# LB77.net
KiCad netlist of a schematic drawn in Altium Designer
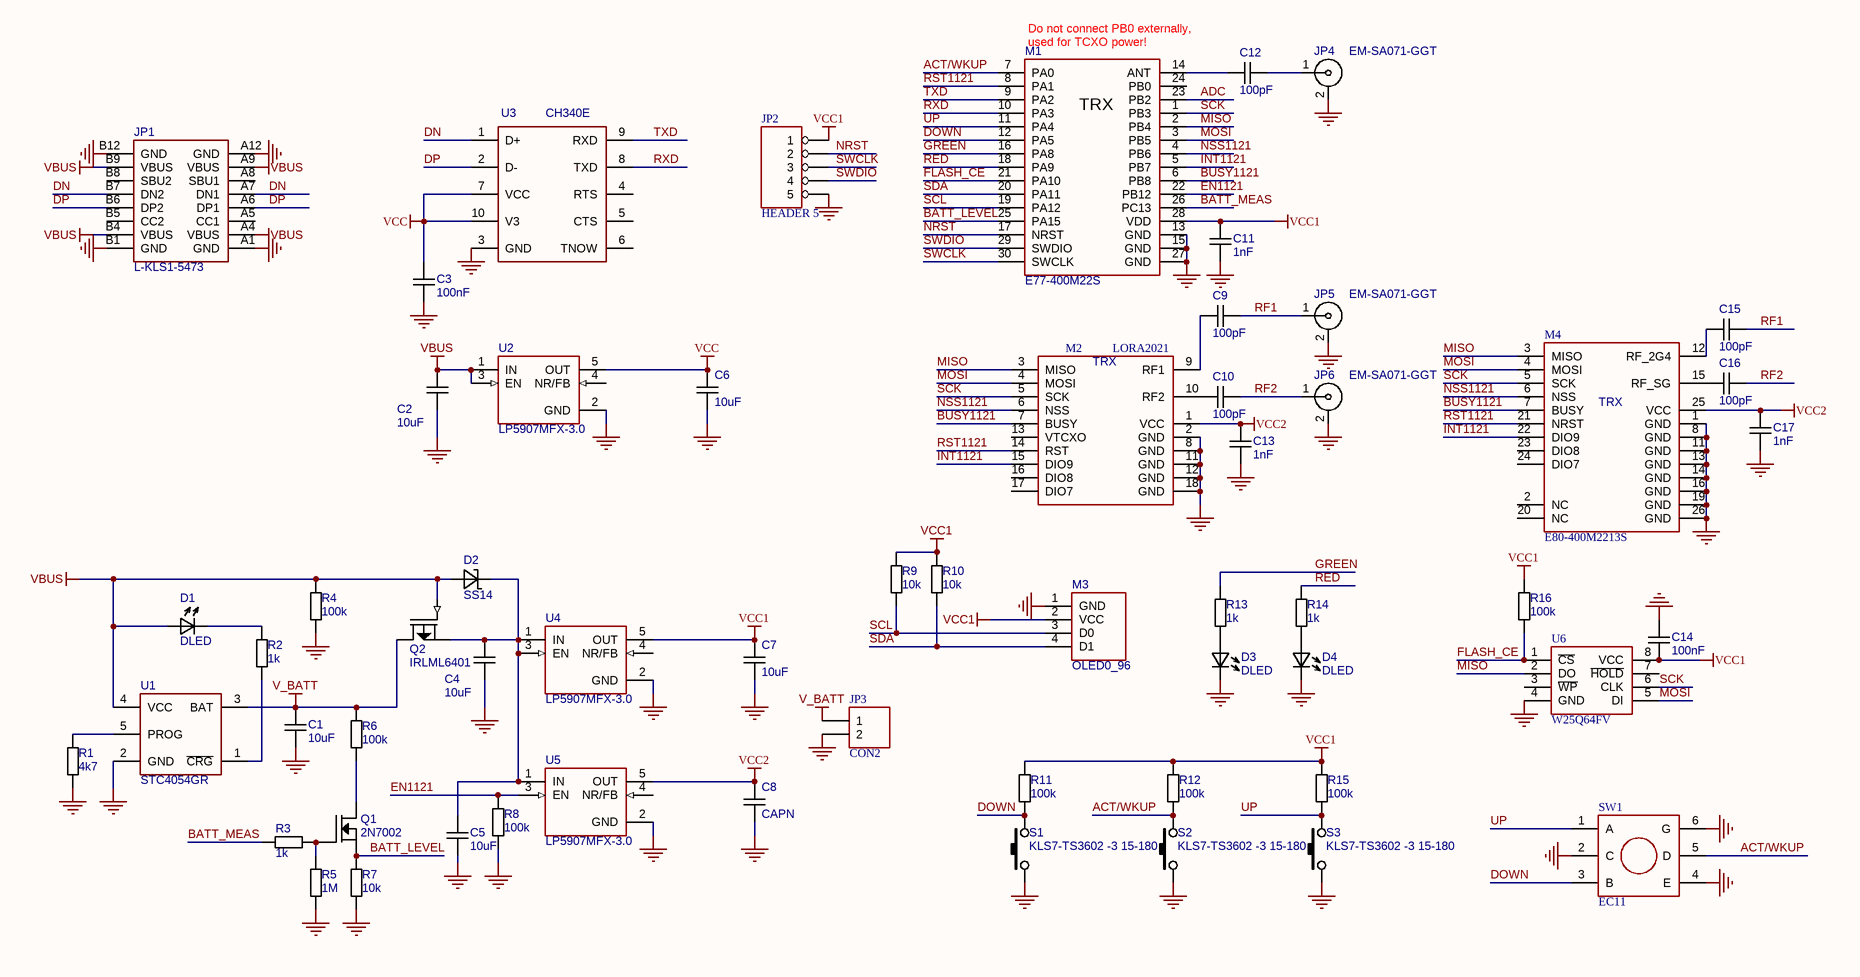
[diagram p0: LB77.SchDoc]

(export (version "E")
  (design (tool "Eeschema 10.0.6"))
  (components
    (comp (ref "C1")
      (value "10uF")
      (footprint "C-0805")
      (fields (field (name "VOLTAGE") "50V"))
      (libsource (lib "Passive") (part "CAPN"))
    )
    (comp (ref "C2")
      (value "10uF")
      (footprint "C-0805")
      (fields (field (name "VOLTAGE") "50V"))
      (libsource (lib "Passive") (part "CAPN"))
    )
    (comp (ref "C3")
      (value "100nF")
      (footprint "C-0603")
      (fields (field (name "VOLTAGE") "50V"))
      (libsource (lib "Passive") (part "CAPN"))
    )
    (comp (ref "C4")
      (value "10uF")
      (footprint "C-0805")
      (fields (field (name "VOLTAGE") "50V"))
      (libsource (lib "Passive") (part "CAPN"))
    )
    (comp (ref "C5")
      (value "10uF")
      (footprint "C-0805")
      (fields (field (name "VOLTAGE") "50V"))
      (libsource (lib "Passive") (part "CAPN"))
    )
    (comp (ref "C6")
      (value "10uF")
      (footprint "C-0805")
      (fields (field (name "VOLTAGE") "50V"))
      (libsource (lib "Passive") (part "CAPN"))
    )
    (comp (ref "C7")
      (value "10uF")
      (footprint "C-0805")
      (fields (field (name "VOLTAGE") "50V"))
      (libsource (lib "Passive") (part "CAPN"))
    )
    (comp (ref "C8")
      (value "CAPN")
      (footprint "C-0805")
      (fields (field (name "VOLTAGE") "50V"))
      (libsource (lib "Passive") (part "CAPN"))
    )
    (comp (ref "C9")
      (value "100pF")
      (footprint "C-0603")
      (fields (field (name "VOLTAGE") "50V"))
      (libsource (lib "Passive") (part "CAPN"))
    )
    (comp (ref "C10")
      (value "100pF")
      (footprint "C-0603")
      (fields (field (name "VOLTAGE") "50V"))
      (libsource (lib "Passive") (part "CAPN"))
    )
    (comp (ref "C11")
      (value "1nF")
      (footprint "C-0603")
      (fields (field (name "VOLTAGE") "50V"))
      (libsource (lib "Passive") (part "CAPN"))
    )
    (comp (ref "C12")
      (value "100pF")
      (footprint "C-0603")
      (fields (field (name "VOLTAGE") "50V"))
      (libsource (lib "Passive") (part "CAPN"))
    )
    (comp (ref "C13")
      (value "1nF")
      (footprint "C-0603")
      (fields (field (name "VOLTAGE") "50V"))
      (libsource (lib "Passive") (part "CAPN"))
    )
    (comp (ref "C14")
      (value "100nF")
      (footprint "C-0603")
      (fields (field (name "VOLTAGE") "50V"))
      (libsource (lib "Passive") (part "CAPN"))
    )
    (comp (ref "C15")
      (value "100pF")
      (footprint "C-0603")
      (fields (field (name "VOLTAGE") "50V"))
      (libsource (lib "Passive") (part "CAPN"))
    )
    (comp (ref "C16")
      (value "100pF")
      (footprint "C-0603")
      (fields (field (name "VOLTAGE") "50V"))
      (libsource (lib "Passive") (part "CAPN"))
    )
    (comp (ref "C17")
      (value "1nF")
      (footprint "C-0603")
      (fields (field (name "VOLTAGE") "50V"))
      (libsource (lib "Passive") (part "CAPN"))
    )
    (comp (ref "D1") (value "DLED") (footprint "LED_3mm_RED") (libsource (lib "Diodes") (part "DLED")))
    (comp (ref "D2") (value "SS14") (footprint "D-SMA") (libsource (lib "Diodes") (part "DIODSH")))
    (comp (ref "D3") (value "DLED") (footprint "LED_3mm_RED") (libsource (lib "Diodes") (part "DLED")))
    (comp (ref "D4") (value "DLED") (footprint "LED_3mm_RED") (libsource (lib "Diodes") (part "DLED")))
    (comp (ref "JP1")
      (value "L-KLS1-5473")
      (footprint "USB_C_SMD_SLOT")
      (libsource (lib "Connectors") (part "L-KLS1-5473"))
    )
    (comp (ref "JP2")
      (value "HEADER 5")
      (footprint "PLS1-5")
      (libsource (lib "Connectors") (part "HEADER 5"))
    )
    (comp (ref "JP3") (value "CON2") (footprint "WH-02R") (libsource (lib "Connectors") (part "CON2")))
    (comp (ref "JP4")
      (value "EM-SA071-GGT")
      (footprint "SMA_F_EDGE")
      (description "SMA Female R/A PCB Mount")
      (libsource (lib "Connectors") (part "SMA"))
    )
    (comp (ref "JP5")
      (value "EM-SA071-GGT")
      (footprint "SMA_F_EDGE")
      (description "SMA Female R/A PCB Mount")
      (libsource (lib "Connectors") (part "SMA"))
    )
    (comp (ref "JP6")
      (value "EM-SA071-GGT")
      (footprint "SMA_F_EDGE")
      (description "SMA Female R/A PCB Mount")
      (libsource (lib "Connectors") (part "SMA"))
    )
    (comp (ref "M1")
      (value "E77-400M22S")
      (footprint "E77XX-M22")
      (libsource (lib "RFmodules") (part "E77-400M22S"))
    )
    (comp (ref "M2")
      (value "LORA2021")
      (footprint "LORA1121")
      (libsource (lib "RFmodules") (part "LORAXX21"))
    )
    (comp (ref "M3")
      (value "OLED0_96")
      (footprint "OLED096_I2C")
      (libsource (lib "RFmodules") (part "OLED0_96_I2C"))
    )
    (comp (ref "M4") (value "E80-400M2213S") (footprint "E80") (libsource (lib "RFmodules") (part "E80")))
    (comp (ref "Q1") (value "2N7002") (footprint "SOT-23") (libsource (lib "Transistors") (part "MOSF-N")))
    (comp (ref "Q2") (value "IRLML6401") (footprint "SOT-23") (libsource (lib "Discrete") (part "MOSF-P")))
    (comp (ref "R1") (value "4k7") (footprint "R-0603") (libsource (lib "") (part "RES_2")))
    (comp (ref "R2") (value "1k") (footprint "R-0603") (libsource (lib "Passive") (part "RES")))
    (comp (ref "R3") (value "1k") (footprint "R-0603") (libsource (lib "") (part "RES_1")))
    (comp (ref "R4") (value "100k") (footprint "R-0603") (libsource (lib "Passive") (part "RES")))
    (comp (ref "R5") (value "1M") (footprint "R-0603") (libsource (lib "Passive") (part "RES")))
    (comp (ref "R6") (value "100k") (footprint "R-0603") (libsource (lib "Passive") (part "RES")))
    (comp (ref "R7") (value "10k") (footprint "R-0603") (libsource (lib "Passive") (part "RES")))
    (comp (ref "R8") (value "100k") (footprint "R-0603") (libsource (lib "Passive") (part "RES")))
    (comp (ref "R9") (value "10k") (footprint "R-0603") (libsource (lib "Passive") (part "RES")))
    (comp (ref "R10") (value "10k") (footprint "R-0603") (libsource (lib "Passive") (part "RES")))
    (comp (ref "R11") (value "100k") (footprint "R-0603") (libsource (lib "Passive") (part "RES")))
    (comp (ref "R12") (value "100k") (footprint "R-0603") (libsource (lib "Passive") (part "RES")))
    (comp (ref "R13") (value "1k") (footprint "R-0603") (libsource (lib "Passive") (part "RES")))
    (comp (ref "R14") (value "1k") (footprint "R-0603") (libsource (lib "Passive") (part "RES")))
    (comp (ref "R15") (value "100k") (footprint "R-0603") (libsource (lib "Passive") (part "RES")))
    (comp (ref "R16") (value "100k") (footprint "R-0603") (libsource (lib "Passive") (part "RES")))
    (comp (ref "S1")
      (value "KLS7-TS3602 -3 15-180")
      (footprint "KN_MIN")
      (libsource (lib "Switches") (part "SW-1"))
    )
    (comp (ref "S2")
      (value "KLS7-TS3602 -3 15-180")
      (footprint "KN_MIN")
      (libsource (lib "Switches") (part "SW-1"))
    )
    (comp (ref "S3")
      (value "KLS7-TS3602 -3 15-180")
      (footprint "KN_MIN")
      (libsource (lib "Switches") (part "SW-1"))
    )
    (comp (ref "SW1") (value "EC11") (footprint "EC11") (libsource (lib "Switches") (part "EC11")))
    (comp (ref "U1") (value "STC4054GR") (footprint "SOT-23-5") (libsource (lib "Power") (part "STC4054")))
    (comp (ref "U2")
      (value "LP5907MFX-3.0")
      (footprint "SOT-23-5")
      (description "250mA Low-Dropout Regulator")
      (libsource (lib "ICs") (part "LP5907"))
    )
    (comp (ref "U3") (value "CH340E") (footprint "MSOP-10") (libsource (lib "ICs") (part "CH340E")))
    (comp (ref "U4")
      (value "LP5907MFX-3.0")
      (footprint "SOT-23-5")
      (description "250mA Low-Dropout Regulator")
      (libsource (lib "ICs") (part "LP5907"))
    )
    (comp (ref "U5")
      (value "LP5907MFX-3.0")
      (footprint "SOT-23-5")
      (description "250mA Low-Dropout Regulator")
      (libsource (lib "ICs") (part "LP5907"))
    )
    (comp (ref "U6") (value "W25Q64FV") (footprint "SOIC8-208") (libsource (lib "ICs") (part "W25Q64FV")))
  )
  (nets
    (net (code "1") (name "/ACT{slash}WKUP") (class "Default")
      (node (ref "M1") (pin "7") (pinfunction "PA0_7") (pintype "passive"))
      (node (ref "R12") (pin "1") (pinfunction "1_1") (pintype "passive"))
      (node (ref "S2") (pin "2") (pinfunction "2_2") (pintype "passive"))
      (node (ref "SW1") (pin "5") (pinfunction "D_5") (pintype "passive"))
    )
    (net (code "2") (name "/ADC") (class "Default")
      (node (ref "M1") (pin "23") (pinfunction "PB2_23") (pintype "passive"))
    )
    (net (code "3") (name "/BATT_LEVEL") (class "Default")
      (node (ref "M1") (pin "25") (pinfunction "PA15_25") (pintype "passive"))
      (node (ref "Q1") (pin "2") (pinfunction "SOURCE_2") (pintype "passive"))
      (node (ref "R7") (pin "2") (pinfunction "2_2") (pintype "passive"))
    )
    (net (code "4") (name "/BATT_MEAS") (class "Default")
      (node (ref "M1") (pin "26") (pinfunction "PC13_26") (pintype "passive"))
      (node (ref "R3") (pin "2") (pinfunction "2_2") (pintype "passive"))
    )
    (net (code "5") (name "/BUSY1121") (class "Default")
      (node (ref "M1") (pin "6") (pinfunction "PB8_6") (pintype "passive"))
      (node (ref "M2") (pin "7") (pinfunction "BUSY_7") (pintype "passive"))
      (node (ref "M4") (pin "7") (pinfunction "BUSY_7") (pintype "passive"))
    )
    (net (code "6") (name "/DN") (class "Default")
      (node (ref "JP1") (pin "A7") (pinfunction "DN1_A7") (pintype "passive"))
      (node (ref "JP1") (pin "B7") (pinfunction "DN2_B7") (pintype "passive"))
      (node (ref "U3") (pin "1") (pinfunction "D+_1") (pintype "passive"))
    )
    (net (code "7") (name "/DOWN") (class "Default")
      (node (ref "M1") (pin "12") (pinfunction "PA5_12") (pintype "passive"))
      (node (ref "R11") (pin "1") (pinfunction "1_1") (pintype "passive"))
      (node (ref "S1") (pin "2") (pinfunction "2_2") (pintype "passive"))
      (node (ref "SW1") (pin "3") (pinfunction "B_3") (pintype "passive"))
    )
    (net (code "8") (name "/DP") (class "Default")
      (node (ref "JP1") (pin "A6") (pinfunction "DP1_A6") (pintype "passive"))
      (node (ref "JP1") (pin "B6") (pinfunction "DP2_B6") (pintype "passive"))
      (node (ref "U3") (pin "2") (pinfunction "D-_2") (pintype "passive"))
    )
    (net (code "9") (name "/EN1121") (class "Default")
      (node (ref "M1") (pin "22") (pinfunction "PB12_22") (pintype "passive"))
      (node (ref "R8") (pin "2") (pinfunction "2_2") (pintype "passive"))
      (node (ref "U5") (pin "3") (pinfunction "EN_3") (pintype "input"))
    )
    (net (code "10") (name "/FLASH_CE") (class "Default")
      (node (ref "M1") (pin "21") (pinfunction "PA10_21") (pintype "passive"))
      (node (ref "R16") (pin "1") (pinfunction "1_1") (pintype "passive"))
      (node (ref "U6") (pin "1") (pinfunction "~{CS}_1") (pintype "passive"))
    )
    (net (code "11") (name "/GREEN") (class "Default")
      (node (ref "M1") (pin "16") (pinfunction "PA8_16") (pintype "passive"))
      (node (ref "R13") (pin "2") (pinfunction "2_2") (pintype "passive"))
    )
    (net (code "12") (name "/INT1121") (class "Default")
      (node (ref "M1") (pin "5") (pinfunction "PB7_5") (pintype "passive"))
      (node (ref "M2") (pin "15") (pinfunction "DIO9_15") (pintype "passive"))
      (node (ref "M4") (pin "22") (pinfunction "DIO9_22") (pintype "passive"))
    )
    (net (code "13") (name "/MISO") (class "Default")
      (node (ref "M1") (pin "2") (pinfunction "PB4_2") (pintype "passive"))
      (node (ref "M2") (pin "3") (pinfunction "MISO_3") (pintype "passive"))
      (node (ref "M4") (pin "3") (pinfunction "MISO_3") (pintype "passive"))
      (node (ref "U6") (pin "2") (pinfunction "DO_2") (pintype "passive"))
    )
    (net (code "14") (name "/MOSI") (class "Default")
      (node (ref "M1") (pin "3") (pinfunction "PB5_3") (pintype "passive"))
      (node (ref "M2") (pin "4") (pinfunction "MOSI_4") (pintype "passive"))
      (node (ref "M4") (pin "4") (pinfunction "MOSI_4") (pintype "passive"))
      (node (ref "U6") (pin "5") (pinfunction "DI_5") (pintype "passive"))
    )
    (net (code "15") (name "/NRST") (class "Default")
      (node (ref "JP2") (pin "2") (pinfunction "2_2") (pintype "passive"))
      (node (ref "M1") (pin "17") (pinfunction "NRST_17") (pintype "passive"))
    )
    (net (code "16") (name "/NSS1121") (class "Default")
      (node (ref "M1") (pin "4") (pinfunction "PB6_4") (pintype "passive"))
      (node (ref "M2") (pin "6") (pinfunction "NSS_6") (pintype "passive"))
      (node (ref "M4") (pin "6") (pinfunction "NSS_6") (pintype "passive"))
    )
    (net (code "17") (name "/RED") (class "Default")
      (node (ref "M1") (pin "18") (pinfunction "PA9_18") (pintype "passive"))
      (node (ref "R14") (pin "2") (pinfunction "2_2") (pintype "passive"))
    )
    (net (code "18") (name "/RF1") (class "Default")
      (node (ref "C15") (pin "2") (pinfunction "2_2") (pintype "passive"))
      (node (ref "C9") (pin "2") (pinfunction "2_2") (pintype "passive"))
      (node (ref "JP5") (pin "1") (pinfunction "1_1") (pintype "passive"))
    )
    (net (code "19") (name "/RF2") (class "Default")
      (node (ref "C10") (pin "2") (pinfunction "2_2") (pintype "passive"))
      (node (ref "C16") (pin "2") (pinfunction "2_2") (pintype "passive"))
      (node (ref "JP6") (pin "1") (pinfunction "1_1") (pintype "passive"))
    )
    (net (code "20") (name "/RST1121") (class "Default")
      (node (ref "M1") (pin "8") (pinfunction "PA1_8") (pintype "passive"))
      (node (ref "M2") (pin "14") (pinfunction "RST_14") (pintype "passive"))
      (node (ref "M4") (pin "21") (pinfunction "NRST_21") (pintype "passive"))
    )
    (net (code "21") (name "/RXD") (class "Default")
      (node (ref "M1") (pin "10") (pinfunction "PA3_10") (pintype "passive"))
      (node (ref "U3") (pin "8") (pinfunction "TXD_8") (pintype "passive"))
    )
    (net (code "22") (name "/SCK") (class "Default")
      (node (ref "M1") (pin "1") (pinfunction "PB3_1") (pintype "passive"))
      (node (ref "M2") (pin "5") (pinfunction "SCK_5") (pintype "passive"))
      (node (ref "M4") (pin "5") (pinfunction "SCK_5") (pintype "passive"))
      (node (ref "U6") (pin "6") (pinfunction "CLK_6") (pintype "passive"))
    )
    (net (code "23") (name "/SCL") (class "Default")
      (node (ref "M1") (pin "19") (pinfunction "PA12_19") (pintype "passive"))
      (node (ref "M3") (pin "3") (pinfunction "D0_3") (pintype "passive"))
      (node (ref "R9") (pin "1") (pinfunction "1_1") (pintype "passive"))
    )
    (net (code "24") (name "/SDA") (class "Default")
      (node (ref "M1") (pin "20") (pinfunction "PA11_20") (pintype "passive"))
      (node (ref "M3") (pin "4") (pinfunction "D1_4") (pintype "passive"))
      (node (ref "R10") (pin "1") (pinfunction "1_1") (pintype "passive"))
    )
    (net (code "25") (name "/SWCLK") (class "Default")
      (node (ref "JP2") (pin "3") (pinfunction "3_3") (pintype "passive"))
      (node (ref "M1") (pin "30") (pinfunction "SWCLK_30") (pintype "passive"))
    )
    (net (code "26") (name "/SWDIO") (class "Default")
      (node (ref "JP2") (pin "4") (pinfunction "4_4") (pintype "passive"))
      (node (ref "M1") (pin "29") (pinfunction "SWDIO_29") (pintype "passive"))
    )
    (net (code "27") (name "/TXD") (class "Default")
      (node (ref "M1") (pin "9") (pinfunction "PA2_9") (pintype "passive"))
      (node (ref "U3") (pin "9") (pinfunction "RXD_9") (pintype "passive"))
    )
    (net (code "28") (name "/UP") (class "Default")
      (node (ref "M1") (pin "11") (pinfunction "PA4_11") (pintype "passive"))
      (node (ref "R15") (pin "1") (pinfunction "1_1") (pintype "passive"))
      (node (ref "S3") (pin "2") (pinfunction "2_2") (pintype "passive"))
      (node (ref "SW1") (pin "1") (pinfunction "A_1") (pintype "passive"))
    )
    (net (code "29") (name "GND") (class "Default")
      (node (ref "C1") (pin "2") (pinfunction "2_2") (pintype "passive"))
      (node (ref "C11") (pin "2") (pinfunction "2_2") (pintype "passive"))
      (node (ref "C13") (pin "2") (pinfunction "2_2") (pintype "passive"))
      (node (ref "C14") (pin "1") (pinfunction "1_1") (pintype "passive"))
      (node (ref "C17") (pin "2") (pinfunction "2_2") (pintype "passive"))
      (node (ref "C2") (pin "2") (pinfunction "2_2") (pintype "passive"))
      (node (ref "C3") (pin "2") (pinfunction "2_2") (pintype "passive"))
      (node (ref "C4") (pin "2") (pinfunction "2_2") (pintype "passive"))
      (node (ref "C5") (pin "2") (pinfunction "2_2") (pintype "passive"))
      (node (ref "C6") (pin "2") (pinfunction "2_2") (pintype "passive"))
      (node (ref "C7") (pin "2") (pinfunction "2_2") (pintype "passive"))
      (node (ref "C8") (pin "2") (pinfunction "2_2") (pintype "passive"))
      (node (ref "D3") (pin "2") (pinfunction "2_2") (pintype "passive"))
      (node (ref "D4") (pin "2") (pinfunction "2_2") (pintype "passive"))
      (node (ref "JP1") (pin "A1") (pinfunction "GND_A1") (pintype "passive"))
      (node (ref "JP1") (pin "A12") (pinfunction "GND_A12") (pintype "passive"))
      (node (ref "JP1") (pin "B1") (pinfunction "GND_B1") (pintype "passive"))
      (node (ref "JP1") (pin "B12") (pinfunction "GND_B12") (pintype "passive"))
      (node (ref "JP2") (pin "5") (pinfunction "5_5") (pintype "passive"))
      (node (ref "JP3") (pin "2") (pinfunction "2_2") (pintype "passive"))
      (node (ref "JP4") (pin "2") (pinfunction "2_2") (pintype "passive"))
      (node (ref "JP5") (pin "2") (pinfunction "2_2") (pintype "passive"))
      (node (ref "JP6") (pin "2") (pinfunction "2_2") (pintype "passive"))
      (node (ref "M1") (pin "13") (pinfunction "GND_13") (pintype "passive"))
      (node (ref "M1") (pin "15") (pinfunction "GND_15") (pintype "passive"))
      (node (ref "M1") (pin "27") (pinfunction "GND_27") (pintype "passive"))
      (node (ref "M2") (pin "11") (pinfunction "GND_11") (pintype "passive"))
      (node (ref "M2") (pin "12") (pinfunction "GND_12") (pintype "passive"))
      (node (ref "M2") (pin "18") (pinfunction "GND_18") (pintype "passive"))
      (node (ref "M2") (pin "2") (pinfunction "GND_2") (pintype "passive"))
      (node (ref "M2") (pin "8") (pinfunction "GND_8") (pintype "passive"))
      (node (ref "M3") (pin "1") (pinfunction "GND_1") (pintype "passive"))
      (node (ref "M4") (pin "1") (pinfunction "GND_1") (pintype "passive"))
      (node (ref "M4") (pin "11") (pinfunction "GND_11") (pintype "passive"))
      (node (ref "M4") (pin "13") (pinfunction "GND_13") (pintype "passive"))
      (node (ref "M4") (pin "14") (pinfunction "GND_14") (pintype "passive"))
      (node (ref "M4") (pin "16") (pinfunction "GND_16") (pintype "passive"))
      (node (ref "M4") (pin "19") (pinfunction "GND_19") (pintype "passive"))
      (node (ref "M4") (pin "26") (pinfunction "GND_26") (pintype "passive"))
      (node (ref "M4") (pin "8") (pinfunction "GND_8") (pintype "passive"))
      (node (ref "R1") (pin "1") (pinfunction "1_1") (pintype "passive"))
      (node (ref "R4") (pin "1") (pinfunction "1_1") (pintype "passive"))
      (node (ref "R5") (pin "1") (pinfunction "1_1") (pintype "passive"))
      (node (ref "R7") (pin "1") (pinfunction "1_1") (pintype "passive"))
      (node (ref "R8") (pin "1") (pinfunction "1_1") (pintype "passive"))
      (node (ref "S1") (pin "1") (pinfunction "1_1") (pintype "passive"))
      (node (ref "S2") (pin "1") (pinfunction "1_1") (pintype "passive"))
      (node (ref "S3") (pin "1") (pinfunction "1_1") (pintype "passive"))
      (node (ref "SW1") (pin "2") (pinfunction "C_2") (pintype "passive"))
      (node (ref "SW1") (pin "4") (pinfunction "E_4") (pintype "passive"))
      (node (ref "SW1") (pin "6") (pinfunction "G_6") (pintype "passive"))
      (node (ref "U1") (pin "2") (pinfunction "GND_2") (pintype "passive"))
      (node (ref "U2") (pin "2") (pinfunction "GND_2") (pintype "power_in"))
      (node (ref "U3") (pin "3") (pinfunction "GND_3") (pintype "passive"))
      (node (ref "U4") (pin "2") (pinfunction "GND_2") (pintype "power_in"))
      (node (ref "U5") (pin "2") (pinfunction "GND_2") (pintype "power_in"))
      (node (ref "U6") (pin "4") (pinfunction "GND_4") (pintype "passive"))
    )
    (net (code "30") (name "Net-(C12-Pad2)") (class "Default")
      (node (ref "C12") (pin "2") (pinfunction "2_2") (pintype "passive"))
      (node (ref "JP4") (pin "1") (pinfunction "1_1") (pintype "passive"))
    )
    (net (code "31") (name "Net-(D1-Pad2)") (class "Default")
      (node (ref "D1") (pin "2") (pinfunction "2_2") (pintype "passive"))
      (node (ref "R2") (pin "2") (pinfunction "2_2") (pintype "passive"))
    )
    (net (code "32") (name "Net-(D3-Pad1)") (class "Default")
      (node (ref "D3") (pin "1") (pinfunction "1_1") (pintype "passive"))
      (node (ref "R13") (pin "1") (pinfunction "1_1") (pintype "passive"))
    )
    (net (code "33") (name "Net-(D4-Pad1)") (class "Default")
      (node (ref "D4") (pin "1") (pinfunction "1_1") (pintype "passive"))
      (node (ref "R14") (pin "1") (pinfunction "1_1") (pintype "passive"))
    )
    (net (code "34") (name "Net-(M1-ANT)") (class "Default")
      (node (ref "C12") (pin "1") (pinfunction "1_1") (pintype "passive"))
      (node (ref "M1") (pin "14") (pinfunction "ANT_14") (pintype "passive"))
    )
    (net (code "35") (name "Net-(M2-RF1)") (class "Default")
      (node (ref "C9") (pin "1") (pinfunction "1_1") (pintype "passive"))
      (node (ref "M2") (pin "9") (pinfunction "RF1_9") (pintype "passive"))
    )
    (net (code "36") (name "Net-(M2-RF2)") (class "Default")
      (node (ref "C10") (pin "1") (pinfunction "1_1") (pintype "passive"))
      (node (ref "M2") (pin "10") (pinfunction "RF2_10") (pintype "passive"))
    )
    (net (code "37") (name "Net-(M4-RF_2G4)") (class "Default")
      (node (ref "C15") (pin "1") (pinfunction "1_1") (pintype "passive"))
      (node (ref "M4") (pin "12") (pinfunction "RF_2G4_12") (pintype "passive"))
    )
    (net (code "38") (name "Net-(M4-RF_SG)") (class "Default")
      (node (ref "C16") (pin "1") (pinfunction "1_1") (pintype "passive"))
      (node (ref "M4") (pin "15") (pinfunction "RF_SG_15") (pintype "passive"))
    )
    (net (code "39") (name "Net-(Q1-DRAIN)") (class "Default")
      (node (ref "Q1") (pin "3") (pinfunction "DRAIN_3") (pintype "passive"))
      (node (ref "R6") (pin "1") (pinfunction "1_1") (pintype "passive"))
    )
    (net (code "40") (name "Net-(Q1-GATE)") (class "Default")
      (node (ref "Q1") (pin "1") (pinfunction "GATE_1") (pintype "passive"))
      (node (ref "R3") (pin "1") (pinfunction "1_1") (pintype "passive"))
      (node (ref "R5") (pin "2") (pinfunction "2_2") (pintype "passive"))
    )
    (net (code "41") (name "Net-(Q2-SOURCE)") (class "Default")
      (node (ref "C4") (pin "1") (pinfunction "1_1") (pintype "passive"))
      (node (ref "C5") (pin "1") (pinfunction "1_1") (pintype "passive"))
      (node (ref "D2") (pin "2") (pinfunction "2_2") (pintype "passive"))
      (node (ref "Q2") (pin "2") (pinfunction "SOURCE_2") (pintype "passive"))
      (node (ref "U4") (pin "1") (pinfunction "IN_1") (pintype "power_in"))
      (node (ref "U4") (pin "3") (pinfunction "EN_3") (pintype "input"))
      (node (ref "U5") (pin "1") (pinfunction "IN_1") (pintype "power_in"))
    )
    (net (code "42") (name "Net-(U1-PROG)") (class "Default")
      (node (ref "R1") (pin "2") (pinfunction "2_2") (pintype "passive"))
      (node (ref "U1") (pin "5") (pinfunction "PROG_5") (pintype "passive"))
    )
    (net (code "43") (name "Net-(U1-~{CRG})") (class "Default")
      (node (ref "R2") (pin "1") (pinfunction "1_1") (pintype "passive"))
      (node (ref "U1") (pin "1") (pinfunction "~{CRG}_1") (pintype "passive"))
    )
    (net (code "44") (name "VBUS") (class "Default")
      (node (ref "C2") (pin "1") (pinfunction "1_1") (pintype "passive"))
      (node (ref "D1") (pin "1") (pinfunction "1_1") (pintype "passive"))
      (node (ref "D2") (pin "1") (pinfunction "1_1") (pintype "passive"))
      (node (ref "JP1") (pin "A4") (pinfunction "VBUS_A4") (pintype "passive"))
      (node (ref "JP1") (pin "A9") (pinfunction "VBUS_A9") (pintype "passive"))
      (node (ref "JP1") (pin "B4") (pinfunction "VBUS_B4") (pintype "passive"))
      (node (ref "JP1") (pin "B9") (pinfunction "VBUS_B9") (pintype "passive"))
      (node (ref "Q2") (pin "1") (pinfunction "GATE_1") (pintype "input"))
      (node (ref "R4") (pin "2") (pinfunction "2_2") (pintype "passive"))
      (node (ref "U1") (pin "4") (pinfunction "VCC_4") (pintype "passive"))
      (node (ref "U2") (pin "1") (pinfunction "IN_1") (pintype "power_in"))
      (node (ref "U2") (pin "3") (pinfunction "EN_3") (pintype "input"))
    )
    (net (code "45") (name "VCC") (class "Default")
      (node (ref "C3") (pin "1") (pinfunction "1_1") (pintype "passive"))
      (node (ref "C6") (pin "1") (pinfunction "1_1") (pintype "passive"))
      (node (ref "U2") (pin "5") (pinfunction "OUT_5") (pintype "power_in"))
      (node (ref "U3") (pin "10") (pinfunction "V3_10") (pintype "passive"))
      (node (ref "U3") (pin "7") (pinfunction "VCC_7") (pintype "passive"))
    )
    (net (code "46") (name "VCC1") (class "Default")
      (node (ref "C11") (pin "1") (pinfunction "1_1") (pintype "passive"))
      (node (ref "C14") (pin "2") (pinfunction "2_2") (pintype "passive"))
      (node (ref "C7") (pin "1") (pinfunction "1_1") (pintype "passive"))
      (node (ref "JP2") (pin "1") (pinfunction "1_1") (pintype "passive"))
      (node (ref "M1") (pin "28") (pinfunction "VDD_28") (pintype "passive"))
      (node (ref "M3") (pin "2") (pinfunction "VCC_2") (pintype "passive"))
      (node (ref "R10") (pin "2") (pinfunction "2_2") (pintype "passive"))
      (node (ref "R11") (pin "2") (pinfunction "2_2") (pintype "passive"))
      (node (ref "R12") (pin "2") (pinfunction "2_2") (pintype "passive"))
      (node (ref "R15") (pin "2") (pinfunction "2_2") (pintype "passive"))
      (node (ref "R16") (pin "2") (pinfunction "2_2") (pintype "passive"))
      (node (ref "R9") (pin "2") (pinfunction "2_2") (pintype "passive"))
      (node (ref "U4") (pin "5") (pinfunction "OUT_5") (pintype "power_in"))
      (node (ref "U6") (pin "8") (pinfunction "VCC_8") (pintype "passive"))
    )
    (net (code "47") (name "VCC2") (class "Default")
      (node (ref "C13") (pin "1") (pinfunction "1_1") (pintype "passive"))
      (node (ref "C17") (pin "1") (pinfunction "1_1") (pintype "passive"))
      (node (ref "C8") (pin "1") (pinfunction "1_1") (pintype "passive"))
      (node (ref "M2") (pin "1") (pinfunction "VCC_1") (pintype "passive"))
      (node (ref "M4") (pin "25") (pinfunction "VCC_25") (pintype "passive"))
      (node (ref "U5") (pin "5") (pinfunction "OUT_5") (pintype "power_in"))
    )
    (net (code "48") (name "VSS") (class "Default")
      (node (ref "JP1") (pin "17") (pinfunction "VSS_17") (pintype "power_in"))
    )
    (net (code "49") (name "V_BATT") (class "Default")
      (node (ref "C1") (pin "1") (pinfunction "1_1") (pintype "passive"))
      (node (ref "JP3") (pin "1") (pinfunction "1_1") (pintype "passive"))
      (node (ref "Q2") (pin "3") (pinfunction "DRAIN_3") (pintype "passive"))
      (node (ref "R6") (pin "2") (pinfunction "2_2") (pintype "passive"))
      (node (ref "U1") (pin "3") (pinfunction "BAT_3") (pintype "passive"))
    )
    (net (code "50") (name "unconnected-(JP1-CC1-PadA5)") (class "Default")
      (node (ref "JP1") (pin "A5") (pinfunction "CC1_A5") (pintype "passive"))
    )
    (net (code "51") (name "unconnected-(JP1-CC2-PadB5)") (class "Default")
      (node (ref "JP1") (pin "B5") (pinfunction "CC2_B5") (pintype "passive"))
    )
    (net (code "52") (name "unconnected-(JP1-SBU1-PadA8)") (class "Default")
      (node (ref "JP1") (pin "A8") (pinfunction "SBU1_A8") (pintype "passive"))
    )
    (net (code "53") (name "unconnected-(JP1-SBU2-PadB8)") (class "Default")
      (node (ref "JP1") (pin "B8") (pinfunction "SBU2_B8") (pintype "passive"))
    )
    (net (code "54") (name "unconnected-(M1-PB0-Pad24)") (class "Default")
      (node (ref "M1") (pin "24") (pinfunction "PB0_24") (pintype "passive"))
    )
    (net (code "55") (name "unconnected-(M2-DIO7-Pad17)") (class "Default")
      (node (ref "M2") (pin "17") (pinfunction "DIO7_17") (pintype "passive"))
    )
    (net (code "56") (name "unconnected-(M2-DIO8-Pad16)") (class "Default")
      (node (ref "M2") (pin "16") (pinfunction "DIO8_16") (pintype "passive"))
    )
    (net (code "57") (name "unconnected-(M2-VTCXO-Pad13)") (class "Default")
      (node (ref "M2") (pin "13") (pinfunction "VTCXO_13") (pintype "passive"))
    )
    (net (code "58") (name "unconnected-(M4-DIO7-Pad24)") (class "Default")
      (node (ref "M4") (pin "24") (pinfunction "DIO7_24") (pintype "passive"))
    )
    (net (code "59") (name "unconnected-(M4-DIO8-Pad23)") (class "Default")
      (node (ref "M4") (pin "23") (pinfunction "DIO8_23") (pintype "passive"))
    )
    (net (code "60") (name "unconnected-(M4-NC-Pad2)") (class "Default")
      (node (ref "M4") (pin "2") (pinfunction "NC_2") (pintype "passive"))
    )
    (net (code "61") (name "unconnected-(M4-NC-Pad20)") (class "Default")
      (node (ref "M4") (pin "20") (pinfunction "NC_20") (pintype "passive"))
    )
    (net (code "62") (name "unconnected-(U2-NR{slash}FB-Pad4)") (class "Default")
      (node (ref "U2") (pin "4") (pinfunction "NR/FB_4") (pintype "input"))
    )
    (net (code "63") (name "unconnected-(U3-CTS-Pad5)") (class "Default")
      (node (ref "U3") (pin "5") (pinfunction "CTS_5") (pintype "passive"))
    )
    (net (code "64") (name "unconnected-(U3-RTS-Pad4)") (class "Default")
      (node (ref "U3") (pin "4") (pinfunction "RTS_4") (pintype "passive"))
    )
    (net (code "65") (name "unconnected-(U3-TNOW-Pad6)") (class "Default")
      (node (ref "U3") (pin "6") (pinfunction "TNOW_6") (pintype "passive"))
    )
    (net (code "66") (name "unconnected-(U4-NR{slash}FB-Pad4)") (class "Default")
      (node (ref "U4") (pin "4") (pinfunction "NR/FB_4") (pintype "input"))
    )
    (net (code "67") (name "unconnected-(U5-NR{slash}FB-Pad4)") (class "Default")
      (node (ref "U5") (pin "4") (pinfunction "NR/FB_4") (pintype "input"))
    )
    (net (code "68") (name "unconnected-(U6-~{HOLD}-Pad7)") (class "Default")
      (node (ref "U6") (pin "7") (pinfunction "~{HOLD}_7") (pintype "passive"))
    )
    (net (code "69") (name "unconnected-(U6-~{WP}-Pad3)") (class "Default")
      (node (ref "U6") (pin "3") (pinfunction "~{WP}_3") (pintype "passive"))
    )
  )
)
